# IOT-Tower-Light-Rev-A.net
KiCad netlist of a schematic drawn in EAGLE
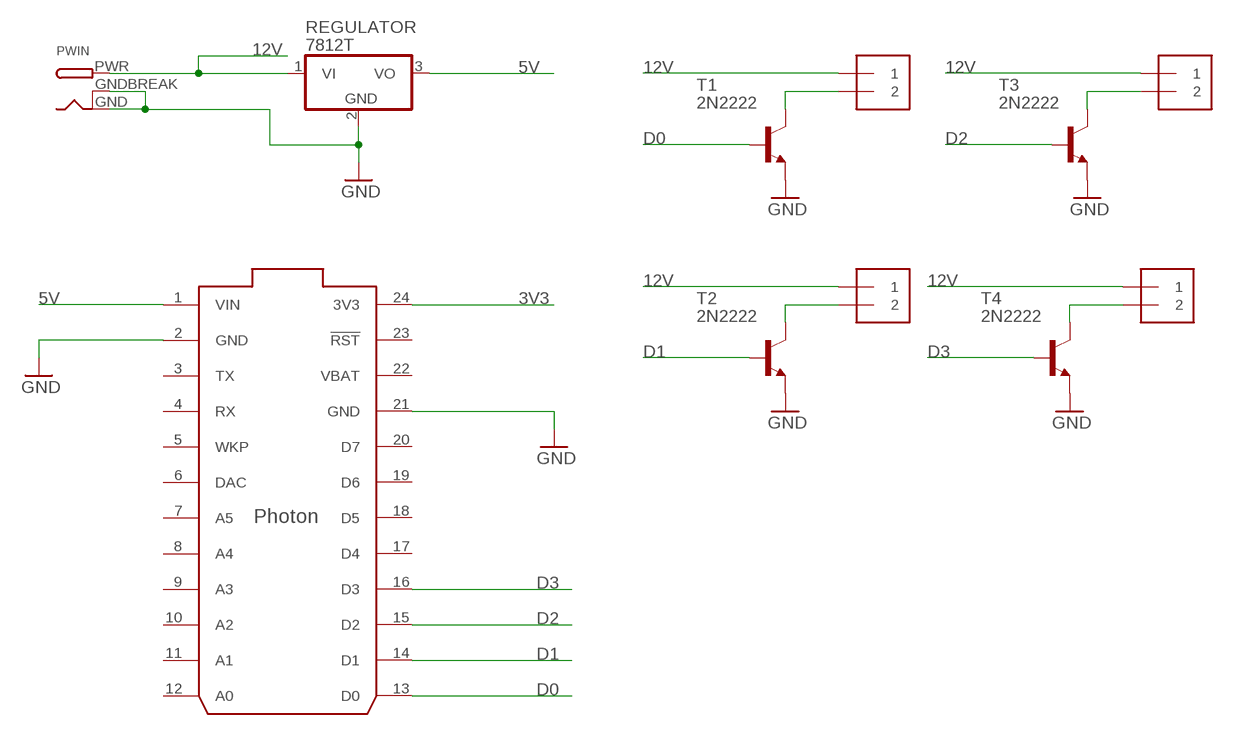
[diagram p0: schematic, sheet 1]

(export (version "E")
  (design (tool "Eeschema 10.0.6"))
  (components
    (comp (ref "BUZZER")
      (value "1X2-3.5MM")
      (footprint "eagle-import:1X2-3.5MM")
      (libsource (lib "eagle-import") (part "1X2-3.5MM"))
    )
    (comp (ref "GREEN")
      (value "1X2-3.5MM")
      (footprint "eagle-import:1X2-3.5MM")
      (libsource (lib "eagle-import") (part "1X2-3.5MM"))
    )
    (comp (ref "PWIN")
      (value "DCBARRELPTH")
      (footprint "eagle-import:DCJACK_2MM_PTH")
      (libsource (lib "eagle-import") (part "DCBARRELPTH"))
    )
    (comp (ref "RED")
      (value "1X2-3.5MM")
      (footprint "eagle-import:1X2-3.5MM")
      (libsource (lib "eagle-import") (part "1X2-3.5MM"))
    )
    (comp (ref "REGULATOR")
      (value "7812T")
      (footprint "eagle-import:TO220H")
      (libsource (lib "eagle-import") (part "78T12"))
    )
    (comp (ref "T1")
      (value "2N2222")
      (footprint "eagle-import:TO92-EBC-OVAL")
      (libsource (lib "eagle-import") (part "2N2222"))
    )
    (comp (ref "T2")
      (value "2N2222")
      (footprint "eagle-import:TO92-EBC-OVAL")
      (libsource (lib "eagle-import") (part "2N2222"))
    )
    (comp (ref "T3")
      (value "2N2222")
      (footprint "eagle-import:TO92-EBC-OVAL")
      (libsource (lib "eagle-import") (part "2N2222"))
    )
    (comp (ref "T4")
      (value "2N2222")
      (footprint "eagle-import:TO92-EBC-OVAL")
      (libsource (lib "eagle-import") (part "2N2222"))
    )
    (comp (ref "U$1")
      (value "PHOTON_WITH_HEADERS")
      (footprint "eagle-import:PHOTON")
      (libsource (lib "eagle-import") (part "PHOTON_WITH_HEADERS"))
    )
    (comp (ref "YELLOW")
      (value "1X2-3.5MM")
      (footprint "eagle-import:1X2-3.5MM")
      (libsource (lib "eagle-import") (part "1X2-3.5MM"))
    )
  )
  (nets
    (net (code "1") (name "/3V3") (class "Default")
      (node (ref "U$1") (pin "24") (pinfunction "3V3_24") (pintype "power_in"))
    )
    (net (code "2") (name "/5V") (class "Default")
      (node (ref "REGULATOR") (pin "3") (pinfunction "VO_3") (pintype "passive"))
      (node (ref "U$1") (pin "1") (pinfunction "VIN_1") (pintype "power_in"))
    )
    (net (code "3") (name "/12V") (class "Default")
      (node (ref "BUZZER") (pin "1") (pinfunction "1_1") (pintype "passive"))
      (node (ref "GREEN") (pin "1") (pinfunction "1_1") (pintype "passive"))
      (node (ref "PWIN") (pin "PWR") (pinfunction "PWR_PWR") (pintype "power_in"))
      (node (ref "RED") (pin "1") (pinfunction "1_1") (pintype "passive"))
      (node (ref "REGULATOR") (pin "1") (pinfunction "VI_1") (pintype "input"))
      (node (ref "YELLOW") (pin "1") (pinfunction "1_1") (pintype "passive"))
    )
    (net (code "4") (name "/D0") (class "Default")
      (node (ref "T1") (pin "B") (pinfunction "B_B") (pintype "passive"))
      (node (ref "U$1") (pin "13") (pinfunction "D0_13") (pintype "bidirectional"))
    )
    (net (code "5") (name "/D1") (class "Default")
      (node (ref "T2") (pin "B") (pinfunction "B_B") (pintype "passive"))
      (node (ref "U$1") (pin "14") (pinfunction "D1_14") (pintype "bidirectional"))
    )
    (net (code "6") (name "/D2") (class "Default")
      (node (ref "T3") (pin "B") (pinfunction "B_B") (pintype "passive"))
      (node (ref "U$1") (pin "15") (pinfunction "D2_15") (pintype "bidirectional"))
    )
    (net (code "7") (name "/D3") (class "Default")
      (node (ref "T4") (pin "B") (pinfunction "B_B") (pintype "passive"))
      (node (ref "U$1") (pin "16") (pinfunction "D3_16") (pintype "bidirectional"))
    )
    (net (code "8") (name "/VBAT") (class "Default")
      (node (ref "U$1") (pin "22") (pinfunction "VBAT_22") (pintype "power_in"))
    )
    (net (code "9") (name "GND") (class "Default")
      (node (ref "PWIN") (pin "GND") (pinfunction "GND_GND") (pintype "power_in"))
      (node (ref "PWIN") (pin "GNDBREAK") (pinfunction "GNDBREAK_GNDBREAK") (pintype "power_in"))
      (node (ref "REGULATOR") (pin "2") (pinfunction "GND_2") (pintype "passive"))
      (node (ref "T1") (pin "E") (pinfunction "E_E") (pintype "passive"))
      (node (ref "T2") (pin "E") (pinfunction "E_E") (pintype "passive"))
      (node (ref "T3") (pin "E") (pinfunction "E_E") (pintype "passive"))
      (node (ref "T4") (pin "E") (pinfunction "E_E") (pintype "passive"))
      (node (ref "U$1") (pin "2") (pinfunction "GND_2") (pintype "power_in"))
      (node (ref "U$1") (pin "21") (pinfunction "GND_21") (pintype "power_in"))
    )
    (net (code "10") (name "Net-(BUZZER-Pad2)") (class "Default")
      (node (ref "BUZZER") (pin "2") (pinfunction "2_2") (pintype "passive"))
      (node (ref "T4") (pin "C") (pinfunction "C_C") (pintype "passive"))
    )
    (net (code "11") (name "Net-(GREEN-Pad2)") (class "Default")
      (node (ref "GREEN") (pin "2") (pinfunction "2_2") (pintype "passive"))
      (node (ref "T3") (pin "C") (pinfunction "C_C") (pintype "passive"))
    )
    (net (code "12") (name "Net-(RED-Pad2)") (class "Default")
      (node (ref "RED") (pin "2") (pinfunction "2_2") (pintype "passive"))
      (node (ref "T1") (pin "C") (pinfunction "C_C") (pintype "passive"))
    )
    (net (code "13") (name "Net-(T2-PadC)") (class "Default")
      (node (ref "T2") (pin "C") (pinfunction "C_C") (pintype "passive"))
      (node (ref "YELLOW") (pin "2") (pinfunction "2_2") (pintype "passive"))
    )
    (net (code "14") (name "unconnected-(U$1-A0-Pad12)") (class "Default")
      (node (ref "U$1") (pin "12") (pinfunction "A0_12") (pintype "bidirectional"))
    )
    (net (code "15") (name "unconnected-(U$1-A1-Pad11)") (class "Default")
      (node (ref "U$1") (pin "11") (pinfunction "A1_11") (pintype "bidirectional"))
    )
    (net (code "16") (name "unconnected-(U$1-A2-Pad10)") (class "Default")
      (node (ref "U$1") (pin "10") (pinfunction "A2_10") (pintype "bidirectional"))
    )
    (net (code "17") (name "unconnected-(U$1-A3-Pad9)") (class "Default")
      (node (ref "U$1") (pin "9") (pinfunction "A3_9") (pintype "bidirectional"))
    )
    (net (code "18") (name "unconnected-(U$1-A4-Pad8)") (class "Default")
      (node (ref "U$1") (pin "8") (pinfunction "A4_8") (pintype "bidirectional"))
    )
    (net (code "19") (name "unconnected-(U$1-A5-Pad7)") (class "Default")
      (node (ref "U$1") (pin "7") (pinfunction "A5_7") (pintype "bidirectional"))
    )
    (net (code "20") (name "unconnected-(U$1-D4-Pad17)") (class "Default")
      (node (ref "U$1") (pin "17") (pinfunction "D4_17") (pintype "bidirectional"))
    )
    (net (code "21") (name "unconnected-(U$1-D5-Pad18)") (class "Default")
      (node (ref "U$1") (pin "18") (pinfunction "D5_18") (pintype "bidirectional"))
    )
    (net (code "22") (name "unconnected-(U$1-D6-Pad19)") (class "Default")
      (node (ref "U$1") (pin "19") (pinfunction "D6_19") (pintype "bidirectional"))
    )
    (net (code "23") (name "unconnected-(U$1-D7-Pad20)") (class "Default")
      (node (ref "U$1") (pin "20") (pinfunction "D7_20") (pintype "bidirectional"))
    )
    (net (code "24") (name "unconnected-(U$1-DAC-Pad6)") (class "Default")
      (node (ref "U$1") (pin "6") (pinfunction "DAC_6") (pintype "bidirectional"))
    )
    (net (code "25") (name "unconnected-(U$1-RX-Pad4)") (class "Default")
      (node (ref "U$1") (pin "4") (pinfunction "RX_4") (pintype "bidirectional"))
    )
    (net (code "26") (name "unconnected-(U$1-TX-Pad3)") (class "Default")
      (node (ref "U$1") (pin "3") (pinfunction "TX_3") (pintype "bidirectional"))
    )
    (net (code "27") (name "unconnected-(U$1-WKP-Pad5)") (class "Default")
      (node (ref "U$1") (pin "5") (pinfunction "WKP_5") (pintype "bidirectional"))
    )
    (net (code "28") (name "unconnected-(U$1-~{RST}-Pad23)") (class "Default")
      (node (ref "U$1") (pin "23") (pinfunction "~{RST}_23") (pintype "bidirectional"))
    )
  )
)
